# microfpga.net
KiCad netlist of a schematic drawn in EAGLE
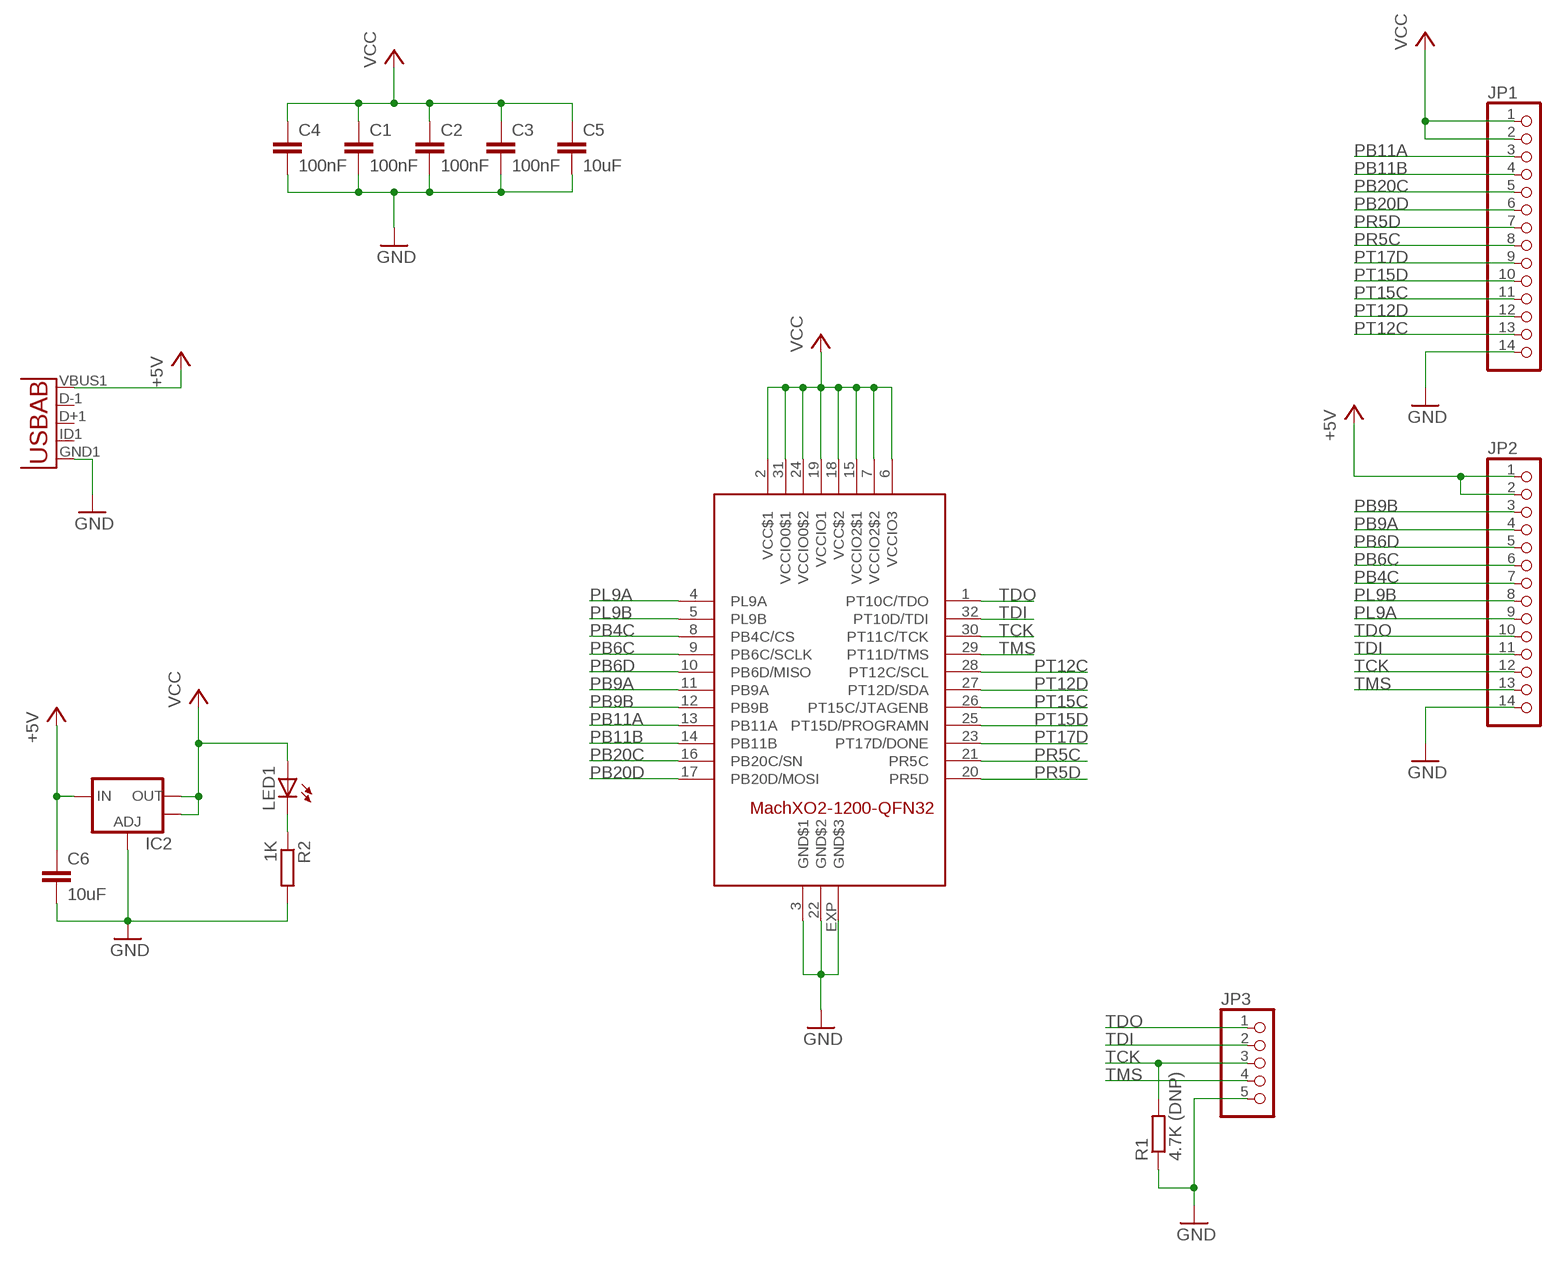
[diagram p0: schematic, sheet 1]

(export (version "E")
  (design (tool "Eeschema 10.0.6"))
  (components
    (comp (ref "C1")
      (value "100nF")
      (footprint "eagle-import:C0603")
      (libsource (lib "eagle-import") (part "C-EUC0603"))
    )
    (comp (ref "C2")
      (value "100nF")
      (footprint "eagle-import:C0603")
      (libsource (lib "eagle-import") (part "C-EUC0603"))
    )
    (comp (ref "C3")
      (value "100nF")
      (footprint "eagle-import:C0603")
      (libsource (lib "eagle-import") (part "C-EUC0603"))
    )
    (comp (ref "C4")
      (value "100nF")
      (footprint "eagle-import:C0603")
      (libsource (lib "eagle-import") (part "C-EUC0603"))
    )
    (comp (ref "C5")
      (value "10uF")
      (footprint "eagle-import:C0805")
      (libsource (lib "eagle-import") (part "C-EUC0805"))
    )
    (comp (ref "C6")
      (value "10uF")
      (footprint "eagle-import:C0805")
      (libsource (lib "eagle-import") (part "C-EUC0805"))
    )
    (comp (ref "IC2")
      (value "V_REG_LM1117SOT223")
      (footprint "eagle-import:SOT223")
      (libsource (lib "eagle-import") (part "V_REG_LM1117SOT223"))
    )
    (comp (ref "JP1")
      (value "PINHD-1X14")
      (footprint "eagle-import:1X14")
      (libsource (lib "eagle-import") (part "PINHD-1X14"))
    )
    (comp (ref "JP2")
      (value "PINHD-1X14")
      (footprint "eagle-import:1X14")
      (libsource (lib "eagle-import") (part "PINHD-1X14"))
    )
    (comp (ref "JP3")
      (value "PINHD-1X5")
      (footprint "eagle-import:1X05")
      (libsource (lib "eagle-import") (part "PINHD-1X5"))
    )
    (comp (ref "LED1")
      (value "LEDCHIPLED_0603")
      (footprint "eagle-import:CHIPLED_0603")
      (libsource (lib "eagle-import") (part "LEDCHIPLED_0603"))
    )
    (comp (ref "R1")
      (value "4.7K (DNP)")
      (footprint "eagle-import:R0603")
      (libsource (lib "eagle-import") (part "R-EU_R0603"))
    )
    (comp (ref "R2")
      (value "1K")
      (footprint "eagle-import:R0603")
      (libsource (lib "eagle-import") (part "R-EU_R0603"))
    )
    (comp (ref "U$1")
      (value "MACHXO2-1200")
      (footprint "eagle-import:QFN32")
      (libsource (lib "eagle-import") (part "MACHXO2-1200"))
    )
    (comp (ref "U2")
      (value "USB\"\"")
      (footprint "eagle-import:USB-MICRO-SMD")
      (libsource (lib "eagle-import") (part "USB{dblquote}{dblquote}"))
    )
  )
  (nets
    (net (code "1") (name "+5V") (class "Default")
      (node (ref "C6") (pin "1") (pinfunction "1_1") (pintype "passive"))
      (node (ref "IC2") (pin "3") (pinfunction "IN_3") (pintype "input"))
      (node (ref "JP2") (pin "1") (pinfunction "1_1") (pintype "passive"))
      (node (ref "JP2") (pin "2") (pinfunction "2_2") (pintype "passive"))
      (node (ref "U2") (pin "VBUS1") (pinfunction "VBUS_VBUS1") (pintype "bidirectional"))
    )
    (net (code "2") (name "/PB4C") (class "Default")
      (node (ref "JP2") (pin "7") (pinfunction "7_7") (pintype "passive"))
      (node (ref "U$1") (pin "8") (pinfunction "PB4C/CS_8") (pintype "bidirectional"))
    )
    (net (code "3") (name "/PB6C") (class "Default")
      (node (ref "JP2") (pin "6") (pinfunction "6_6") (pintype "passive"))
      (node (ref "U$1") (pin "9") (pinfunction "PB6C/SCLK_9") (pintype "bidirectional"))
    )
    (net (code "4") (name "/PB6D") (class "Default")
      (node (ref "JP2") (pin "5") (pinfunction "5_5") (pintype "passive"))
      (node (ref "U$1") (pin "10") (pinfunction "PB6D/MISO_10") (pintype "bidirectional"))
    )
    (net (code "5") (name "/PB9A") (class "Default")
      (node (ref "JP2") (pin "4") (pinfunction "4_4") (pintype "passive"))
      (node (ref "U$1") (pin "11") (pinfunction "PB9A_11") (pintype "bidirectional"))
    )
    (net (code "6") (name "/PB9B") (class "Default")
      (node (ref "JP2") (pin "3") (pinfunction "3_3") (pintype "passive"))
      (node (ref "U$1") (pin "12") (pinfunction "PB9B_12") (pintype "bidirectional"))
    )
    (net (code "7") (name "/PB11A") (class "Default")
      (node (ref "JP1") (pin "3") (pinfunction "3_3") (pintype "passive"))
      (node (ref "U$1") (pin "13") (pinfunction "PB11A_13") (pintype "bidirectional"))
    )
    (net (code "8") (name "/PB11B") (class "Default")
      (node (ref "JP1") (pin "4") (pinfunction "4_4") (pintype "passive"))
      (node (ref "U$1") (pin "14") (pinfunction "PB11B_14") (pintype "bidirectional"))
    )
    (net (code "9") (name "/PB20C") (class "Default")
      (node (ref "JP1") (pin "5") (pinfunction "5_5") (pintype "passive"))
      (node (ref "U$1") (pin "16") (pinfunction "PB20C/SN_16") (pintype "bidirectional"))
    )
    (net (code "10") (name "/PB20D") (class "Default")
      (node (ref "JP1") (pin "6") (pinfunction "6_6") (pintype "passive"))
      (node (ref "U$1") (pin "17") (pinfunction "PB20D/MOSI_17") (pintype "bidirectional"))
    )
    (net (code "11") (name "/PL9A") (class "Default")
      (node (ref "JP2") (pin "9") (pinfunction "9_9") (pintype "passive"))
      (node (ref "U$1") (pin "4") (pinfunction "PL9A_4") (pintype "bidirectional"))
    )
    (net (code "12") (name "/PL9B") (class "Default")
      (node (ref "JP2") (pin "8") (pinfunction "8_8") (pintype "passive"))
      (node (ref "U$1") (pin "5") (pinfunction "PL9B_5") (pintype "bidirectional"))
    )
    (net (code "13") (name "/PR5C") (class "Default")
      (node (ref "JP1") (pin "8") (pinfunction "8_8") (pintype "passive"))
      (node (ref "U$1") (pin "21") (pinfunction "PR5C_21") (pintype "bidirectional"))
    )
    (net (code "14") (name "/PR5D") (class "Default")
      (node (ref "JP1") (pin "7") (pinfunction "7_7") (pintype "passive"))
      (node (ref "U$1") (pin "20") (pinfunction "PR5D_20") (pintype "bidirectional"))
    )
    (net (code "15") (name "/PT12C") (class "Default")
      (node (ref "JP1") (pin "13") (pinfunction "13_13") (pintype "passive"))
      (node (ref "U$1") (pin "28") (pinfunction "PT12C/SCL_28") (pintype "bidirectional"))
    )
    (net (code "16") (name "/PT12D") (class "Default")
      (node (ref "JP1") (pin "12") (pinfunction "12_12") (pintype "passive"))
      (node (ref "U$1") (pin "27") (pinfunction "PT12D/SDA_27") (pintype "bidirectional"))
    )
    (net (code "17") (name "/PT15C") (class "Default")
      (node (ref "JP1") (pin "11") (pinfunction "11_11") (pintype "passive"))
      (node (ref "U$1") (pin "26") (pinfunction "PT15C/JTAGENB_26") (pintype "bidirectional"))
    )
    (net (code "18") (name "/PT15D") (class "Default")
      (node (ref "JP1") (pin "10") (pinfunction "10_10") (pintype "passive"))
      (node (ref "U$1") (pin "25") (pinfunction "PT15D/PROGRAMN_25") (pintype "bidirectional"))
    )
    (net (code "19") (name "/PT17D") (class "Default")
      (node (ref "JP1") (pin "9") (pinfunction "9_9") (pintype "passive"))
      (node (ref "U$1") (pin "23") (pinfunction "PT17D/DONE_23") (pintype "bidirectional"))
    )
    (net (code "20") (name "/TCK") (class "Default")
      (node (ref "JP2") (pin "12") (pinfunction "12_12") (pintype "passive"))
      (node (ref "JP3") (pin "3") (pinfunction "3_3") (pintype "passive"))
      (node (ref "R1") (pin "2") (pinfunction "2_2") (pintype "passive"))
      (node (ref "U$1") (pin "30") (pinfunction "PT11C/TCK_30") (pintype "bidirectional"))
    )
    (net (code "21") (name "/TDI") (class "Default")
      (node (ref "JP2") (pin "11") (pinfunction "11_11") (pintype "passive"))
      (node (ref "JP3") (pin "2") (pinfunction "2_2") (pintype "passive"))
      (node (ref "U$1") (pin "32") (pinfunction "PT10D/TDI_32") (pintype "bidirectional"))
    )
    (net (code "22") (name "/TDO") (class "Default")
      (node (ref "JP2") (pin "10") (pinfunction "10_10") (pintype "passive"))
      (node (ref "JP3") (pin "1") (pinfunction "1_1") (pintype "passive"))
      (node (ref "U$1") (pin "1") (pinfunction "PT10C/TDO_1") (pintype "bidirectional"))
    )
    (net (code "23") (name "/TMS") (class "Default")
      (node (ref "JP2") (pin "13") (pinfunction "13_13") (pintype "passive"))
      (node (ref "JP3") (pin "4") (pinfunction "4_4") (pintype "passive"))
      (node (ref "U$1") (pin "29") (pinfunction "PT11D/TMS_29") (pintype "bidirectional"))
    )
    (net (code "24") (name "GND") (class "Default")
      (node (ref "C1") (pin "2") (pinfunction "2_2") (pintype "passive"))
      (node (ref "C2") (pin "2") (pinfunction "2_2") (pintype "passive"))
      (node (ref "C3") (pin "2") (pinfunction "2_2") (pintype "passive"))
      (node (ref "C4") (pin "2") (pinfunction "2_2") (pintype "passive"))
      (node (ref "C5") (pin "2") (pinfunction "2_2") (pintype "passive"))
      (node (ref "C6") (pin "2") (pinfunction "2_2") (pintype "passive"))
      (node (ref "IC2") (pin "1") (pinfunction "ADJ_1") (pintype "input"))
      (node (ref "JP1") (pin "14") (pinfunction "14_14") (pintype "passive"))
      (node (ref "JP2") (pin "14") (pinfunction "14_14") (pintype "passive"))
      (node (ref "JP3") (pin "5") (pinfunction "5_5") (pintype "passive"))
      (node (ref "R1") (pin "1") (pinfunction "1_1") (pintype "passive"))
      (node (ref "R2") (pin "2") (pinfunction "2_2") (pintype "passive"))
      (node (ref "U$1") (pin "22") (pinfunction "GND$2_22") (pintype "power_in"))
      (node (ref "U$1") (pin "3") (pinfunction "GND$1_3") (pintype "power_in"))
      (node (ref "U$1") (pin "EXP") (pinfunction "GND$3_EXP") (pintype "power_in"))
      (node (ref "U2") (pin "GND1") (pinfunction "GND_GND1") (pintype "bidirectional"))
    )
    (net (code "25") (name "Net-(LED1-PadC)") (class "Default")
      (node (ref "LED1") (pin "C") (pinfunction "C_C") (pintype "passive"))
      (node (ref "R2") (pin "1") (pinfunction "1_1") (pintype "passive"))
    )
    (net (code "26") (name "VCC") (class "Default")
      (node (ref "C1") (pin "1") (pinfunction "1_1") (pintype "passive"))
      (node (ref "C2") (pin "1") (pinfunction "1_1") (pintype "passive"))
      (node (ref "C3") (pin "1") (pinfunction "1_1") (pintype "passive"))
      (node (ref "C4") (pin "1") (pinfunction "1_1") (pintype "passive"))
      (node (ref "C5") (pin "1") (pinfunction "1_1") (pintype "passive"))
      (node (ref "IC2") (pin "2") (pinfunction "OUT_2") (pintype "output"))
      (node (ref "IC2") (pin "4") (pinfunction "OUT_4") (pintype "output"))
      (node (ref "JP1") (pin "1") (pinfunction "1_1") (pintype "passive"))
      (node (ref "JP1") (pin "2") (pinfunction "2_2") (pintype "passive"))
      (node (ref "LED1") (pin "A") (pinfunction "A_A") (pintype "passive"))
      (node (ref "U$1") (pin "15") (pinfunction "VCCIO2$1_15") (pintype "power_in"))
      (node (ref "U$1") (pin "18") (pinfunction "VCC$2_18") (pintype "power_in"))
      (node (ref "U$1") (pin "19") (pinfunction "VCCIO1_19") (pintype "power_in"))
      (node (ref "U$1") (pin "2") (pinfunction "VCC$1_2") (pintype "power_in"))
      (node (ref "U$1") (pin "24") (pinfunction "VCCIO0$2_24") (pintype "power_in"))
      (node (ref "U$1") (pin "31") (pinfunction "VCCIO0$1_31") (pintype "power_in"))
      (node (ref "U$1") (pin "6") (pinfunction "VCCIO3_6") (pintype "power_in"))
      (node (ref "U$1") (pin "7") (pinfunction "VCCIO2$2_7") (pintype "power_in"))
    )
    (net (code "27") (name "unconnected-(U2-D+-PadD+1)") (class "Default")
      (node (ref "U2") (pin "D+1") (pinfunction "D+_D+1") (pintype "bidirectional"))
    )
    (net (code "28") (name "unconnected-(U2-D--PadD-1)") (class "Default")
      (node (ref "U2") (pin "D-1") (pinfunction "D-_D-1") (pintype "bidirectional"))
    )
    (net (code "29") (name "unconnected-(U2-USBID-PadID1)") (class "Default")
      (node (ref "U2") (pin "ID1") (pinfunction "USBID_ID1") (pintype "bidirectional"))
    )
  )
)
